# Misc.net
KiCad netlist of a schematic drawn in Altium Designer
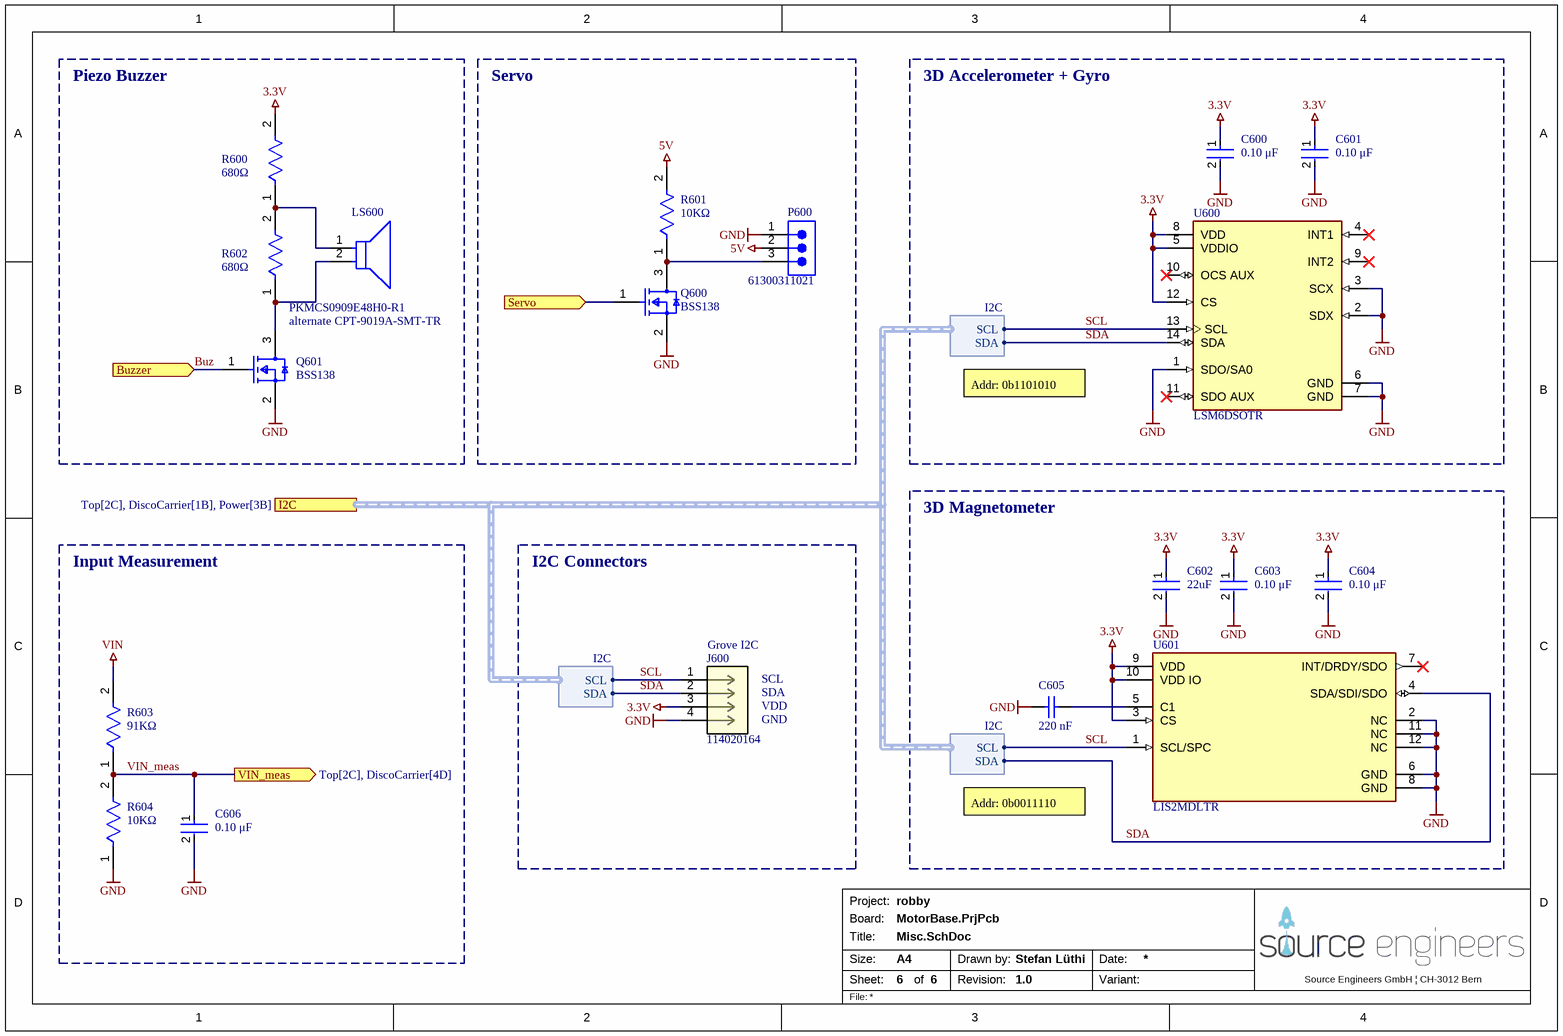
[diagram p0: Misc.SchDoc]

(export (version "E")
  (design (tool "Eeschema 10.0.6"))
  (components
    (comp (ref "C600")
      (value "0.10 μF")
      (footprint "FP-C0603C-CF-MFG")
      (description "CAP CER 0.1UF 50V 20% X7R 0603")
      (fields
        (field (name "MANUFACTURER PART NUMBER") "C0603C104M5RACTU")
        (field (name "MANUFACTURER") "KEMET")
      )
      (libsource (lib "Altium Content Vault") (part "b4654b650e69147ec39a6b967a45e02"))
    )
    (comp (ref "C601")
      (value "0.10 μF")
      (footprint "FP-C0603C-CF-MFG")
      (description "CAP CER 0.1UF 50V 20% X7R 0603")
      (fields
        (field (name "MANUFACTURER PART NUMBER") "C0603C104M5RACTU")
        (field (name "MANUFACTURER") "KEMET")
      )
      (libsource (lib "Altium Content Vault") (part "b4654b650e69147ec39a6b967a45e02"))
    )
    (comp (ref "C602")
      (value "GRM319R61C226ME15D")
      (footprint "FP-GRM319-0_15-IPC_C")
      (description "Chip Multilayer Ceramic Capacitors for General Purpose, 1206, 22uF, X5R, 15%, 20%, 16V")
      (fields (field (name "TOLERANCE") "20%") (field (name "CAPACITANCE") "22uF"))
      (libsource (lib "Altium Content Vault") (part "b4654b650e69147ec39a6b967a45e02"))
    )
    (comp (ref "C603")
      (value "0.10 μF")
      (footprint "FP-C0603C-CF-MFG")
      (description "CAP CER 0.1UF 50V 20% X7R 0603")
      (fields
        (field (name "MANUFACTURER PART NUMBER") "C0603C104M5RACTU")
        (field (name "MANUFACTURER") "KEMET")
      )
      (libsource (lib "Altium Content Vault") (part "b4654b650e69147ec39a6b967a45e02"))
    )
    (comp (ref "C604")
      (value "0.10 μF")
      (footprint "FP-C0603C-CF-MFG")
      (description "CAP CER 0.1UF 50V 20% X7R 0603")
      (fields
        (field (name "MANUFACTURER PART NUMBER") "C0603C104M5RACTU")
        (field (name "MANUFACTURER") "KEMET")
      )
      (libsource (lib "Altium Content Vault") (part "b4654b650e69147ec39a6b967a45e02"))
    )
    (comp (ref "C605")
      (value "220 nF")
      (footprint "CAPC1608X90X35NL15T15")
      (fields (field (name "PART NUMBER") "C0603C224Z4VACTU") (field (name "MANUFACTURER") "Kemet"))
      (libsource (lib "Altium Content Vault") (part "CAP"))
    )
    (comp (ref "C606")
      (value "0.10 μF")
      (footprint "FP-C0603C-CF-MFG")
      (description "CAP CER 0.1UF 50V 20% X7R 0603")
      (fields
        (field (name "MANUFACTURER PART NUMBER") "C0603C104M5RACTU")
        (field (name "MANUFACTURER") "KEMET")
      )
      (libsource (lib "Altium Content Vault") (part "b4654b650e69147ec39a6b967a45e02"))
    )
    (comp (ref "J600")
      (value "114020164")
      (footprint "CONN4_20164_SEE")
      (description "No Description Available")
      (fields (field (name "COPYRIGHT") "Copyright (C) 2025 Ultra Librarian. All rights reserved."))
      (libsource (lib "robby") (part "114020164"))
    )
    (comp (ref "LS600")
      (value "PKMCS0909E48H0-R1")
      (footprint "FP-PKMCS0909E48H0-R1-MFG")
      (description "9.09.0MM 4.8KHZ PIEZOELECTRIC SO")
      (libsource (lib "Altium Content Vault") (part "5f581d31613f872430949aa526fd155"))
    )
    (comp (ref "P600")
      (value "61300311021")
      (footprint "61300311021")
      (libsource (lib "Altium Content Vault") (part "Header_Male_1R_03P"))
    )
    (comp (ref "Q600")
      (value "BSS138")
      (footprint "FP-318-08-IPC_B")
      (description "MOSFET N-CH 50V 220MA SOT-23")
      (libsource (lib "Altium Content Vault") (part "3b9c635fedb024a5347a57b145af9cc"))
    )
    (comp (ref "Q601")
      (value "BSS138")
      (footprint "FP-318-08-IPC_B")
      (description "MOSFET N-CH 50V 220MA SOT-23")
      (libsource (lib "Altium Content Vault") (part "3b9c635fedb024a5347a57b145af9cc"))
    )
    (comp (ref "R600")
      (value "680Ω")
      (footprint "FP-RT0603-MFG")
      (description "RES SMD 680 OHM 1% 1/10W 0603")
      (fields (field (name "MANUFACTURER") "Yageo") (field (name "TOLERANCE") "0.01"))
      (libsource (lib "Altium Content Vault") (part "1029c3af85768c4190bb7ad29bc67b5"))
    )
    (comp (ref "R601")
      (value "10KΩ")
      (footprint "FP-RT0603-MFG")
      (description "RES SMD 10K OHM 1% 1/10W 0603")
      (fields
        (field (name "MANUFACTURER") "Yageo")
        (field (name "OCTOPART") "https://octopart.com/rt0603fre0710kl-yageo-40009243")
      )
      (libsource (lib "Altium Content Vault") (part "1029c3af85768c4190bb7ad29bc67b5"))
    )
    (comp (ref "R602")
      (value "680Ω")
      (footprint "FP-RT0603-MFG")
      (description "RES SMD 680 OHM 1% 1/10W 0603")
      (fields (field (name "MANUFACTURER") "Yageo") (field (name "TOLERANCE") "0.01"))
      (libsource (lib "Altium Content Vault") (part "1029c3af85768c4190bb7ad29bc67b5"))
    )
    (comp (ref "R603")
      (value "RT0603FRE0791KL")
      (footprint "FP-RT0603-MFG")
      (description "RES SMD 91K OHM 1% 1/10W 0603")
      (fields
        (field (name "RESISTANCE") "91KΩ")
        (field (name "MANUFACTURER") "Yageo")
        (field (name "TOLERANCE") "0.01")
      )
      (libsource (lib "Altium Content Vault") (part "1029c3af85768c4190bb7ad29bc67b5"))
    )
    (comp (ref "R604")
      (value "10KΩ")
      (footprint "FP-RT0603-MFG")
      (description "RES SMD 10K OHM 1% 1/10W 0603")
      (fields
        (field (name "MANUFACTURER") "Yageo")
        (field (name "OCTOPART") "https://octopart.com/rt0603fre0710kl-yageo-40009243")
      )
      (libsource (lib "Altium Content Vault") (part "1029c3af85768c4190bb7ad29bc67b5"))
    )
    (comp (ref "U600")
      (value "LSM6DSOTR")
      (footprint "FP-LGA-14L-DM00249496-MFG")
      (description "CONSUMER MEMS")
      (fields
        (field (name "OCTOPART") "https://octopart.com/lsm6dsotr-stmicroelectronics-81706672")
        (field (name "MANUFACTURER") "STMicroelectronics")
      )
      (libsource (lib "Altium Content Vault") (part "2908151a9596ea8f46216e3a0605c49"))
    )
    (comp (ref "U601")
      (value "LIS2MDLTR")
      (footprint "FP-LGA-12-DM00170568-MFG")
      (description "SENSOR MR I2C/SPI 12LGA")
      (fields
        (field (name "OCTOPART") "https://octopart.com/lis2mdltr-stmicroelectronics-81117311")
        (field (name "MANUFACTURER") "STMicroelectronics")
      )
      (libsource (lib "Altium Content Vault") (part "91637d6a6da3cb2d69b1e7726cd74d2"))
    )
  )
  (nets
    (net (code "2") (name "/Buz") (class "Default")
      (node (ref "Q601") (pin "1") (pinfunction "G_1") (pintype "passive"))
    )
    (net (code "3") (name "/SCL") (class "Default")
      (node (ref "J600") (pin "1") (pinfunction "1_1") (pintype "passive"))
      (node (ref "U600") (pin "13") (pinfunction "SCL_13") (pintype "input"))
      (node (ref "U601") (pin "1") (pinfunction "SCL/SPC_1") (pintype "input"))
    )
    (net (code "4") (name "/SDA") (class "Default")
      (node (ref "J600") (pin "2") (pinfunction "2_2") (pintype "passive"))
      (node (ref "U600") (pin "14") (pinfunction "SDA_14") (pintype "bidirectional"))
      (node (ref "U601") (pin "4") (pinfunction "SDA/SDI/SDO_4") (pintype "bidirectional"))
    )
    (net (code "5") (name "/Servo") (class "Default")
      (node (ref "Q600") (pin "1") (pinfunction "G_1") (pintype "passive"))
    )
    (net (code "6") (name "/VIN_meas") (class "Default")
      (node (ref "C606") (pin "1") (pinfunction "1_1") (pintype "passive"))
      (node (ref "R603") (pin "1") (pinfunction "1_1") (pintype "passive"))
      (node (ref "R604") (pin "2") (pinfunction "2_2") (pintype "passive"))
    )
    (net (code "8") (name "3.3V") (class "Default")
      (node (ref "C600") (pin "1") (pinfunction "1_1") (pintype "passive"))
      (node (ref "C601") (pin "1") (pinfunction "1_1") (pintype "passive"))
      (node (ref "C602") (pin "1") (pinfunction "1_1") (pintype "passive"))
      (node (ref "C603") (pin "1") (pinfunction "1_1") (pintype "passive"))
      (node (ref "C604") (pin "1") (pinfunction "1_1") (pintype "passive"))
      (node (ref "J600") (pin "3") (pinfunction "3_3") (pintype "passive"))
      (node (ref "R600") (pin "2") (pinfunction "2_2") (pintype "passive"))
      (node (ref "U600") (pin "12") (pinfunction "CS_12") (pintype "input"))
      (node (ref "U600") (pin "5") (pinfunction "VDDIO_5") (pintype "power_in"))
      (node (ref "U600") (pin "8") (pinfunction "VDD_8") (pintype "power_in"))
      (node (ref "U601") (pin "10") (pinfunction "VDD_IO_10") (pintype "power_in"))
      (node (ref "U601") (pin "3") (pinfunction "CS_3") (pintype "input"))
      (node (ref "U601") (pin "9") (pinfunction "VDD_9") (pintype "power_in"))
    )
    (net (code "9") (name "5V") (class "Default")
      (node (ref "P600") (pin "2") (pinfunction "2_2") (pintype "passive"))
      (node (ref "R601") (pin "2") (pinfunction "2_2") (pintype "passive"))
    )
    (net (code "10") (name "GND") (class "Default")
      (node (ref "C600") (pin "2") (pinfunction "2_2") (pintype "passive"))
      (node (ref "C601") (pin "2") (pinfunction "2_2") (pintype "passive"))
      (node (ref "C602") (pin "2") (pinfunction "2_2") (pintype "passive"))
      (node (ref "C603") (pin "2") (pinfunction "2_2") (pintype "passive"))
      (node (ref "C604") (pin "2") (pinfunction "2_2") (pintype "passive"))
      (node (ref "C605") (pin "1") (pinfunction "1_1") (pintype "passive"))
      (node (ref "C606") (pin "2") (pinfunction "2_2") (pintype "passive"))
      (node (ref "J600") (pin "4") (pinfunction "4_4") (pintype "passive"))
      (node (ref "P600") (pin "1") (pinfunction "1_1") (pintype "passive"))
      (node (ref "Q600") (pin "2") (pinfunction "S_2") (pintype "passive"))
      (node (ref "Q601") (pin "2") (pinfunction "S_2") (pintype "passive"))
      (node (ref "R604") (pin "1") (pinfunction "1_1") (pintype "passive"))
      (node (ref "U600") (pin "1") (pinfunction "SDO/SA0_1") (pintype "input"))
      (node (ref "U600") (pin "2") (pinfunction "SDX_2") (pintype "input"))
      (node (ref "U600") (pin "3") (pinfunction "SCX_3") (pintype "input"))
      (node (ref "U600") (pin "6") (pinfunction "GND_6") (pintype "power_in"))
      (node (ref "U600") (pin "7") (pinfunction "GND_7") (pintype "power_in"))
      (node (ref "U601") (pin "11") (pinfunction "NC_11") (pintype "passive"))
      (node (ref "U601") (pin "12") (pinfunction "NC_12") (pintype "passive"))
      (node (ref "U601") (pin "2") (pinfunction "NC_2") (pintype "passive"))
      (node (ref "U601") (pin "6") (pinfunction "GND_6") (pintype "power_in"))
      (node (ref "U601") (pin "8") (pinfunction "GND_8") (pintype "power_in"))
    )
    (net (code "11") (name "Net-(LS600-Pad1)") (class "Default")
      (node (ref "LS600") (pin "1") (pinfunction "1_1") (pintype "passive"))
      (node (ref "R600") (pin "1") (pinfunction "1_1") (pintype "passive"))
      (node (ref "R602") (pin "2") (pinfunction "2_2") (pintype "passive"))
    )
    (net (code "12") (name "Net-(Q600-D)") (class "Default")
      (node (ref "P600") (pin "3") (pinfunction "3_3") (pintype "passive"))
      (node (ref "Q600") (pin "3") (pinfunction "D_3") (pintype "passive"))
      (node (ref "R601") (pin "1") (pinfunction "1_1") (pintype "passive"))
    )
    (net (code "13") (name "Net-(Q601-D)") (class "Default")
      (node (ref "LS600") (pin "2") (pinfunction "2_2") (pintype "passive"))
      (node (ref "Q601") (pin "3") (pinfunction "D_3") (pintype "passive"))
      (node (ref "R602") (pin "1") (pinfunction "1_1") (pintype "passive"))
    )
    (net (code "14") (name "Net-(U601-C1)") (class "Default")
      (node (ref "C605") (pin "2") (pinfunction "2_2") (pintype "passive"))
      (node (ref "U601") (pin "5") (pinfunction "C1_5") (pintype "passive"))
    )
    (net (code "15") (name "VIN") (class "Default")
      (node (ref "R603") (pin "2") (pinfunction "2_2") (pintype "passive"))
    )
    (net (code "16") (name "unconnected-(U600-INT1-Pad4)") (class "Default")
      (node (ref "U600") (pin "4") (pinfunction "INT1_4") (pintype "input+no_connect"))
    )
    (net (code "17") (name "unconnected-(U600-INT2-Pad9)") (class "Default")
      (node (ref "U600") (pin "9") (pinfunction "INT2_9") (pintype "input+no_connect"))
    )
    (net (code "18") (name "unconnected-(U600-OCS_AUX-Pad10)") (class "Default")
      (node (ref "U600") (pin "10") (pinfunction "OCS_AUX_10") (pintype "bidirectional+no_connect"))
    )
    (net (code "19") (name "unconnected-(U600-SDO_AUX-Pad11)") (class "Default")
      (node (ref "U600") (pin "11") (pinfunction "SDO_AUX_11") (pintype "bidirectional+no_connect"))
    )
    (net (code "20") (name "unconnected-(U601-INT{slash}DRDY{slash}SDO-Pad7)") (class "Default")
      (node (ref "U601") (pin "7") (pinfunction "INT/DRDY/SDO_7") (pintype "output+no_connect"))
    )
  )
)
